# sch.net
KiCad netlist of a schematic drawn in EAGLE
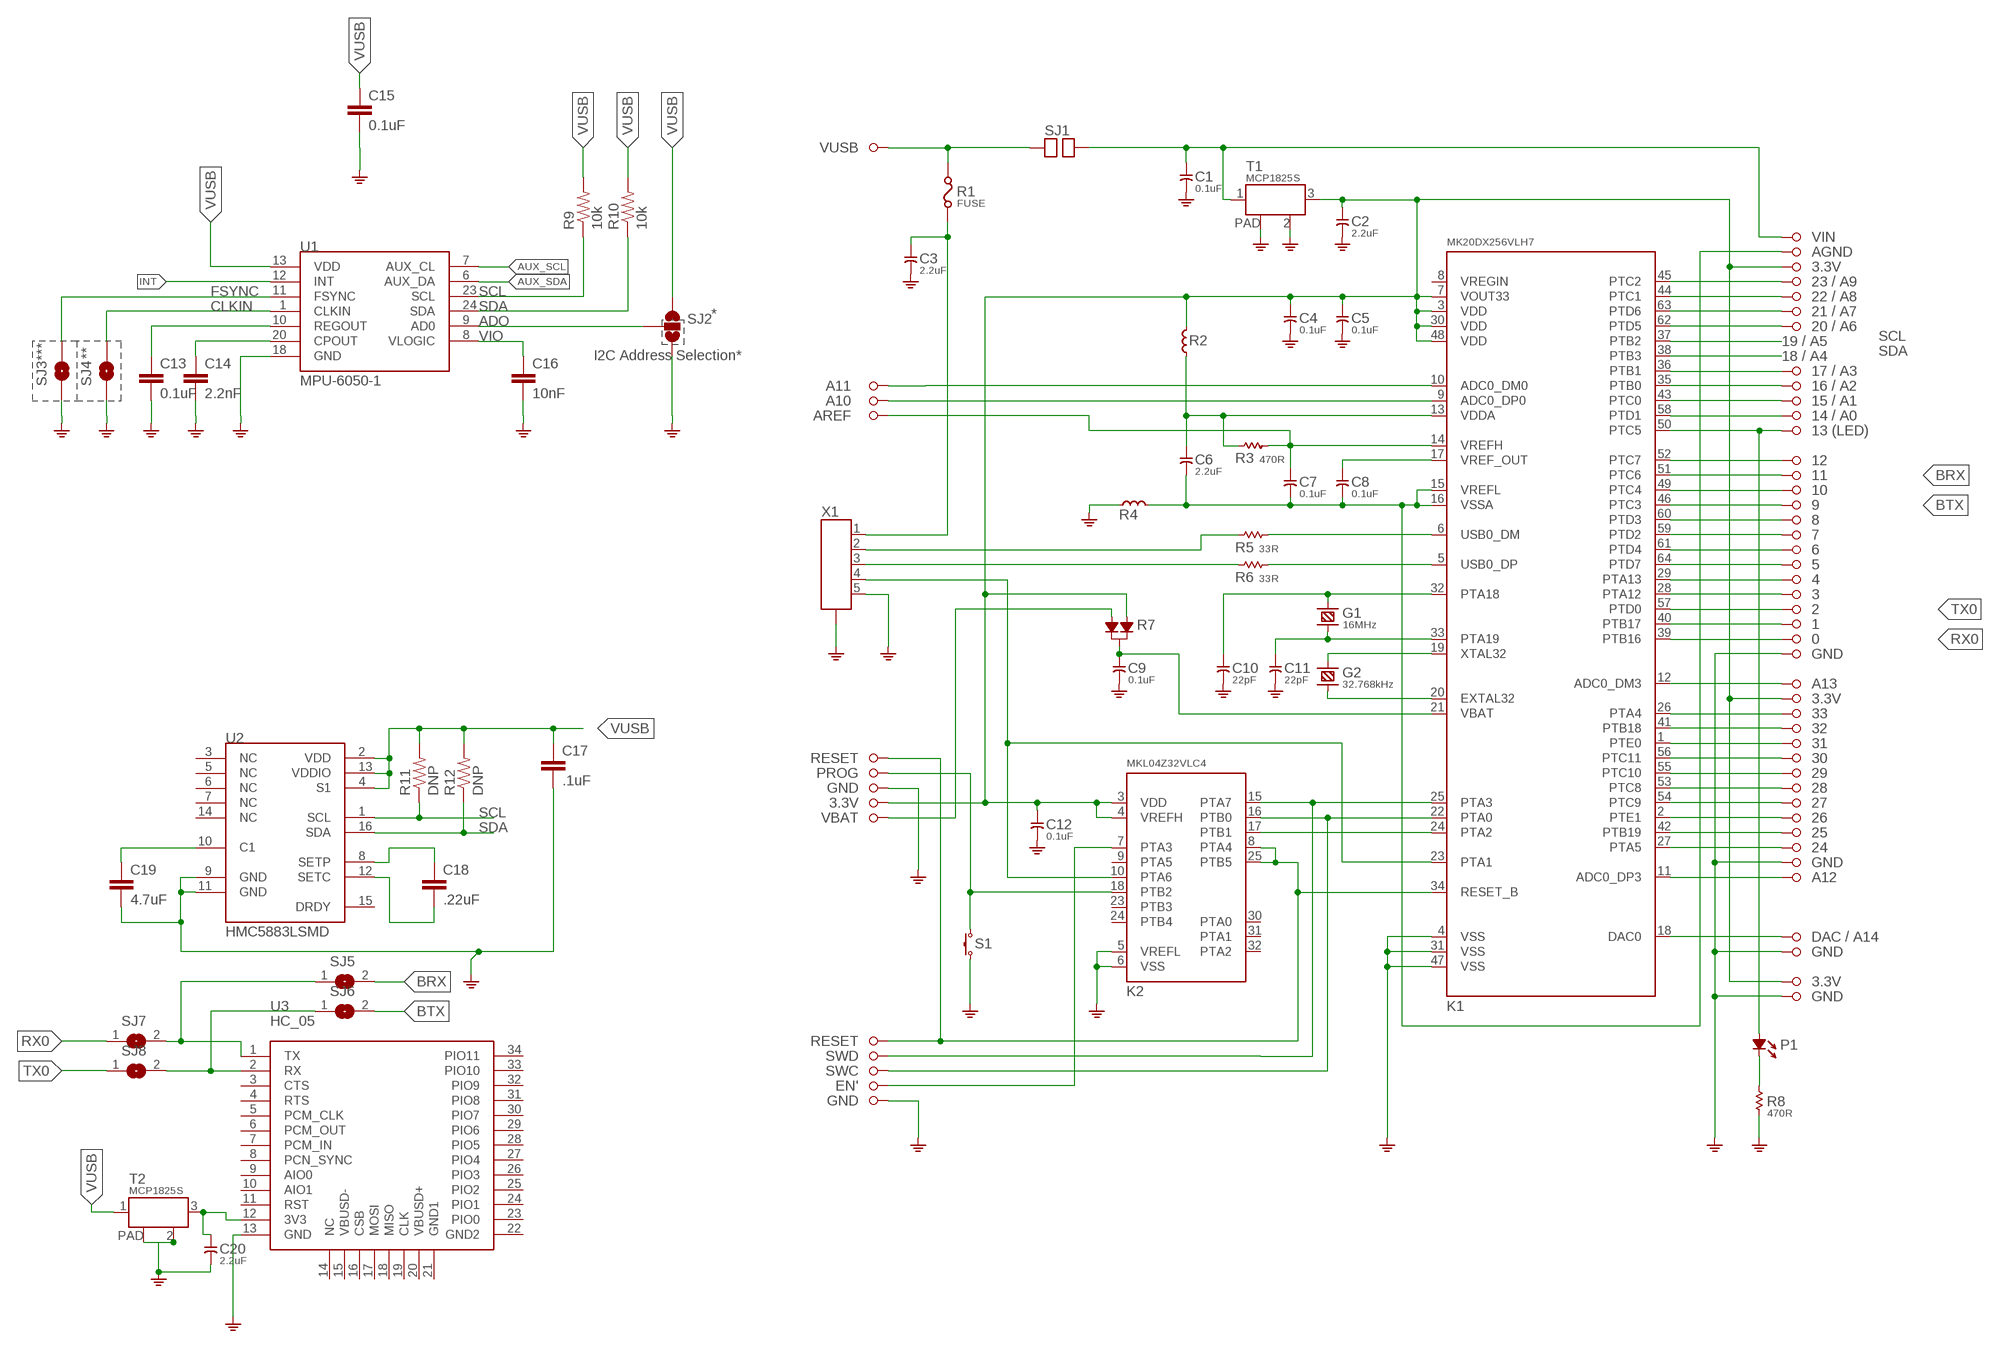
[diagram p0: schematic, sheet 1]

(export (version "E")
  (design (tool "Eeschema 10.0.6"))
  (components
    (comp (ref "C1")
      (value "0.1uF")
      (footprint "eagle-import:C0603")
      (fields (field (name "MF") "Murata Electronics") (field (name "MPN") "GRM188R71C104KA01D"))
      (libsource (lib "eagle-import") (part "CAPACITOR-0.1UF"))
    )
    (comp (ref "C2")
      (value "2.2uF")
      (footprint "eagle-import:C0805")
      (fields (field (name "MF") "Taiyo Yuden") (field (name "MPN") "TMK212B7225KG-TR"))
      (libsource (lib "eagle-import") (part "CAPACITOR-2.2UF"))
    )
    (comp (ref "C3")
      (value "2.2uF")
      (footprint "eagle-import:C0805")
      (fields (field (name "MF") "Taiyo Yuden") (field (name "MPN") "TMK212B7225KG-TR"))
      (libsource (lib "eagle-import") (part "CAPACITOR-2.2UF"))
    )
    (comp (ref "C4")
      (value "0.1uF")
      (footprint "eagle-import:C0603")
      (fields (field (name "MF") "Murata Electronics") (field (name "MPN") "GRM188R71C104KA01D"))
      (libsource (lib "eagle-import") (part "CAPACITOR-0.1UF"))
    )
    (comp (ref "C5")
      (value "0.1uF")
      (footprint "eagle-import:C0603")
      (fields (field (name "MF") "Murata Electronics") (field (name "MPN") "GRM188R71C104KA01D"))
      (libsource (lib "eagle-import") (part "CAPACITOR-0.1UF"))
    )
    (comp (ref "C6")
      (value "2.2uF")
      (footprint "eagle-import:C0805")
      (fields (field (name "MF") "Taiyo Yuden") (field (name "MPN") "TMK212B7225KG-TR"))
      (libsource (lib "eagle-import") (part "CAPACITOR-2.2UF"))
    )
    (comp (ref "C7")
      (value "0.1uF")
      (footprint "eagle-import:C0603")
      (fields (field (name "MF") "Murata Electronics") (field (name "MPN") "GRM188R71C104KA01D"))
      (libsource (lib "eagle-import") (part "CAPACITOR-0.1UF"))
    )
    (comp (ref "C8")
      (value "0.1uF")
      (footprint "eagle-import:C0603")
      (fields (field (name "MF") "Murata Electronics") (field (name "MPN") "GRM188R71C104KA01D"))
      (libsource (lib "eagle-import") (part "CAPACITOR-0.1UF"))
    )
    (comp (ref "C9")
      (value "0.1uF")
      (footprint "eagle-import:C0603")
      (fields (field (name "MF") "Murata Electronics") (field (name "MPN") "GRM188R71C104KA01D"))
      (libsource (lib "eagle-import") (part "CAPACITOR-0.1UF"))
    )
    (comp (ref "C10")
      (value "22pF")
      (footprint "eagle-import:C0603")
      (fields (field (name "MF") "Vishay / Vitramon") (field (name "MPN") "VJ0603A220JXACW1BC"))
      (libsource (lib "eagle-import") (part "CAPACITOR-22PF"))
    )
    (comp (ref "C11")
      (value "22pF")
      (footprint "eagle-import:C0603")
      (fields (field (name "MF") "Vishay / Vitramon") (field (name "MPN") "VJ0603A220JXACW1BC"))
      (libsource (lib "eagle-import") (part "CAPACITOR-22PF"))
    )
    (comp (ref "C12")
      (value "0.1uF")
      (footprint "eagle-import:C0603")
      (fields (field (name "MF") "Murata Electronics") (field (name "MPN") "GRM188R71C104KA01D"))
      (libsource (lib "eagle-import") (part "CAPACITOR-0.1UF"))
    )
    (comp (ref "C13")
      (value "0.1uF")
      (footprint "eagle-import:0603-CAP")
      (libsource (lib "eagle-import") (part "CAP0603-CAP"))
    )
    (comp (ref "C14")
      (value "2.2nF")
      (footprint "eagle-import:0603-CAP")
      (libsource (lib "eagle-import") (part "CAP0603-CAP"))
    )
    (comp (ref "C15")
      (value "0.1uF")
      (footprint "eagle-import:0603-CAP")
      (libsource (lib "eagle-import") (part "CAP0603-CAP"))
    )
    (comp (ref "C16")
      (value "10nF")
      (footprint "eagle-import:0603-CAP")
      (libsource (lib "eagle-import") (part "CAP0603-CAP"))
    )
    (comp (ref "C17")
      (value ".1uF")
      (footprint "eagle-import:0402-CAP")
      (libsource (lib "eagle-import") (part "CAP0402-CAP"))
    )
    (comp (ref "C18")
      (value ".22uF")
      (footprint "eagle-import:0402-CAP")
      (libsource (lib "eagle-import") (part "CAP0402-CAP"))
    )
    (comp (ref "C19")
      (value "4.7uF")
      (footprint "eagle-import:0402-CAP")
      (libsource (lib "eagle-import") (part "CAP0402-CAP"))
    )
    (comp (ref "C20")
      (value "2.2uF")
      (footprint "eagle-import:C0805")
      (fields (field (name "MF") "Taiyo Yuden") (field (name "MPN") "TMK212B7225KG-TR"))
      (libsource (lib "eagle-import") (part "CAPACITOR-2.2UF"))
    )
    (comp (ref "G1")
      (value "16MHz")
      (footprint "eagle-import:HC49US")
      (fields (field (name "MF") "ABRACON") (field (name "MPN") "ABL-16.000MHz-B1U"))
      (libsource (lib "eagle-import") (part "CRYSTAL-HC49US"))
    )
    (comp (ref "G2")
      (value "32.768kHz")
      (footprint "eagle-import:TC26H")
      (fields (field (name "MF") "Citizen FineDevice") (field (name "MPN") " CFS206-32.768KDZF-UB"))
      (libsource (lib "eagle-import") (part "CRYSTAL-TC26H"))
    )
    (comp (ref "K1")
      (value "MK20DX256VLH7")
      (footprint "eagle-import:LQFP64-05")
      (fields (field (name "MF") "NXP"))
      (libsource (lib "eagle-import") (part "MK20DX256VLH7"))
    )
    (comp (ref "K2")
      (value "MKL04Z32VLC4")
      (footprint "eagle-import:LQFP32-08")
      (fields (field (name "MF") "PJRC") (field (name "MPN") "IC_MKL04Z32_TQFP32"))
      (libsource (lib "eagle-import") (part "MKL04Z32VLC4"))
    )
    (comp (ref "P1")
      (value "LED")
      (footprint "eagle-import:LED-0805")
      (fields (field (name "MF") "ROHM Semiconductor") (field (name "MPN") "SML-211DTT86"))
      (libsource (lib "eagle-import") (part "LED"))
    )
    (comp (ref "R1")
      (value "FUSE")
      (footprint "eagle-import:F0805")
      (fields (field (name "MF") "Bel Fuse") (field (name "MPN") "0ZCK0050FF2E"))
      (libsource (lib "eagle-import") (part "FUSE"))
    )
    (comp (ref "R2")
      (value "FERRITE")
      (footprint "eagle-import:L0603")
      (fields (field (name "MF") "Murata Electronics") (field (name "MPN") " BLM18AG601SN1D"))
      (libsource (lib "eagle-import") (part "FERRITE"))
    )
    (comp (ref "R3")
      (value "470R")
      (footprint "eagle-import:R0603")
      (fields (field (name "MF") "Vishay") (field (name "MPN") "CRCW0603470RFKEA"))
      (libsource (lib "eagle-import") (part "RESISTOR-470R"))
    )
    (comp (ref "R4")
      (value "FERRITE")
      (footprint "eagle-import:L0603")
      (fields (field (name "MF") "Murata Electronics") (field (name "MPN") " BLM18AG601SN1D"))
      (libsource (lib "eagle-import") (part "FERRITE"))
    )
    (comp (ref "R5")
      (value "33R")
      (footprint "eagle-import:R0603")
      (fields (field (name "MF") "Panasonic") (field (name "MPN") "ERJ-PA3F33R0V"))
      (libsource (lib "eagle-import") (part "RESISTOR-33R"))
    )
    (comp (ref "R6")
      (value "33R")
      (footprint "eagle-import:R0603")
      (fields (field (name "MF") "Panasonic") (field (name "MPN") "ERJ-PA3F33R0V"))
      (libsource (lib "eagle-import") (part "RESISTOR-33R"))
    )
    (comp (ref "R7")
      (value "DIODE_DUAL")
      (footprint "eagle-import:SOT-23")
      (fields (field (name "MF") "NXP Semiconductors") (field (name "MPN") "BAT54C,215"))
      (libsource (lib "eagle-import") (part "DIODE_DUAL"))
    )
    (comp (ref "R8")
      (value "470R")
      (footprint "eagle-import:R0603")
      (fields (field (name "MF") "Vishay") (field (name "MPN") "CRCW0603470RFKEA"))
      (libsource (lib "eagle-import") (part "RESISTOR-470R"))
    )
    (comp (ref "R9")
      (value "10k")
      (footprint "eagle-import:0603-RES")
      (libsource (lib "eagle-import") (part "RESISTOR0603-RES"))
    )
    (comp (ref "R10")
      (value "10k")
      (footprint "eagle-import:0603-RES")
      (libsource (lib "eagle-import") (part "RESISTOR0603-RES"))
    )
    (comp (ref "R11")
      (value "DNP")
      (footprint "eagle-import:0402-RES")
      (libsource (lib "eagle-import") (part "RESISTOR0402-RES"))
    )
    (comp (ref "R12")
      (value "DNP")
      (footprint "eagle-import:0402-RES")
      (libsource (lib "eagle-import") (part "RESISTOR0402-RES"))
    )
    (comp (ref "S1")
      (value "TACT_SWITCH")
      (footprint "eagle-import:ALPS_SKHH")
      (fields (field (name "MF") "ALPS") (field (name "MPN") "SKHHPKA010"))
      (libsource (lib "eagle-import") (part "TACT_SWITCH"))
    )
    (comp (ref "SJ1")
      (value "SOLDERJUMPER")
      (footprint "eagle-import:SOLDERJUMPER")
      (libsource (lib "eagle-import") (part "SOLDERJUMPER"))
    )
    (comp (ref "SJ2")
      (value "SOLDERJUMPER_2WAYPASTE2&3")
      (footprint "eagle-import:SJ_3_PASTE2&3")
      (libsource (lib "eagle-import") (part "SOLDERJUMPER_2WAYPASTE2&3"))
    )
    (comp (ref "SJ3")
      (value "SOLDERJUMPERTRACE")
      (footprint "eagle-import:SJ_2S-TRACE")
      (libsource (lib "eagle-import") (part "SOLDERJUMPERTRACE"))
    )
    (comp (ref "SJ4")
      (value "SOLDERJUMPERTRACE")
      (footprint "eagle-import:SJ_2S-TRACE")
      (libsource (lib "eagle-import") (part "SOLDERJUMPERTRACE"))
    )
    (comp (ref "SJ5") (value "SJ") (footprint "eagle-import:SJ") (libsource (lib "eagle-import") (part "SJ")))
    (comp (ref "SJ6") (value "SJ") (footprint "eagle-import:SJ") (libsource (lib "eagle-import") (part "SJ")))
    (comp (ref "SJ7") (value "SJ") (footprint "eagle-import:SJ") (libsource (lib "eagle-import") (part "SJ")))
    (comp (ref "SJ8") (value "SJ") (footprint "eagle-import:SJ") (libsource (lib "eagle-import") (part "SJ")))
    (comp (ref "SX1")
      (value "PIN")
      (footprint "eagle-import:PTH_39MIL")
      (libsource (lib "eagle-import") (part "PIN"))
    )
    (comp (ref "SX2")
      (value "PIN")
      (footprint "eagle-import:PTH_39MIL")
      (libsource (lib "eagle-import") (part "PIN"))
    )
    (comp (ref "SX3")
      (value "PIN")
      (footprint "eagle-import:PTH_39MIL")
      (libsource (lib "eagle-import") (part "PIN"))
    )
    (comp (ref "SX4")
      (value "PIN")
      (footprint "eagle-import:PTH_39MIL")
      (libsource (lib "eagle-import") (part "PIN"))
    )
    (comp (ref "SX5")
      (value "PIN")
      (footprint "eagle-import:PTH_39MIL")
      (libsource (lib "eagle-import") (part "PIN"))
    )
    (comp (ref "SX6")
      (value "PIN")
      (footprint "eagle-import:PTH_39MIL")
      (libsource (lib "eagle-import") (part "PIN"))
    )
    (comp (ref "SX7")
      (value "PIN")
      (footprint "eagle-import:PTH_39MIL")
      (libsource (lib "eagle-import") (part "PIN"))
    )
    (comp (ref "SX8")
      (value "PIN")
      (footprint "eagle-import:PTH_39MIL")
      (libsource (lib "eagle-import") (part "PIN"))
    )
    (comp (ref "SX11")
      (value "PIN")
      (footprint "eagle-import:PTH_39MIL")
      (libsource (lib "eagle-import") (part "PIN"))
    )
    (comp (ref "SX12")
      (value "PIN")
      (footprint "eagle-import:PTH_39MIL")
      (libsource (lib "eagle-import") (part "PIN"))
    )
    (comp (ref "SX13")
      (value "PIN")
      (footprint "eagle-import:PTH_39MIL")
      (libsource (lib "eagle-import") (part "PIN"))
    )
    (comp (ref "SX14")
      (value "PIN")
      (footprint "eagle-import:PTH_39MIL")
      (libsource (lib "eagle-import") (part "PIN"))
    )
    (comp (ref "SX15")
      (value "PIN")
      (footprint "eagle-import:PTH_39MIL")
      (libsource (lib "eagle-import") (part "PIN"))
    )
    (comp (ref "SX16")
      (value "PIN")
      (footprint "eagle-import:PTH_39MIL")
      (libsource (lib "eagle-import") (part "PIN"))
    )
    (comp (ref "SX17")
      (value "PIN")
      (footprint "eagle-import:PTH_39MIL")
      (libsource (lib "eagle-import") (part "PIN"))
    )
    (comp (ref "SX18")
      (value "PIN")
      (footprint "eagle-import:PTH_39MIL")
      (libsource (lib "eagle-import") (part "PIN"))
    )
    (comp (ref "SX19")
      (value "PIN")
      (footprint "eagle-import:PTH_39MIL")
      (libsource (lib "eagle-import") (part "PIN"))
    )
    (comp (ref "SX20")
      (value "PIN")
      (footprint "eagle-import:PTH_39MIL")
      (libsource (lib "eagle-import") (part "PIN"))
    )
    (comp (ref "SX21")
      (value "PIN")
      (footprint "eagle-import:PTH_39MIL")
      (libsource (lib "eagle-import") (part "PIN"))
    )
    (comp (ref "SX22")
      (value "PIN")
      (footprint "eagle-import:PTH_39MIL")
      (libsource (lib "eagle-import") (part "PIN"))
    )
    (comp (ref "SX23")
      (value "PIN")
      (footprint "eagle-import:PTH_39MIL")
      (libsource (lib "eagle-import") (part "PIN"))
    )
    (comp (ref "SX24")
      (value "PIN")
      (footprint "eagle-import:PTH_39MIL")
      (libsource (lib "eagle-import") (part "PIN"))
    )
    (comp (ref "SX25")
      (value "PIN")
      (footprint "eagle-import:PTH_39MIL")
      (libsource (lib "eagle-import") (part "PIN"))
    )
    (comp (ref "SX26")
      (value "PIN")
      (footprint "eagle-import:PTH_39MIL")
      (libsource (lib "eagle-import") (part "PIN"))
    )
    (comp (ref "SX27")
      (value "PIN")
      (footprint "eagle-import:PTH_39MIL")
      (libsource (lib "eagle-import") (part "PIN"))
    )
    (comp (ref "SX28")
      (value "PIN")
      (footprint "eagle-import:PTH_39MIL")
      (libsource (lib "eagle-import") (part "PIN"))
    )
    (comp (ref "SX29")
      (value "PIN")
      (footprint "eagle-import:PTH_39MIL")
      (libsource (lib "eagle-import") (part "PIN"))
    )
    (comp (ref "SX30")
      (value "PIN")
      (footprint "eagle-import:PTH_39MIL")
      (libsource (lib "eagle-import") (part "PIN"))
    )
    (comp (ref "SX31")
      (value "PIN")
      (footprint "eagle-import:PTH_39MIL")
      (libsource (lib "eagle-import") (part "PIN"))
    )
    (comp (ref "SX32")
      (value "PIN")
      (footprint "eagle-import:PTH_39MIL")
      (libsource (lib "eagle-import") (part "PIN"))
    )
    (comp (ref "SX33")
      (value "PIN")
      (footprint "eagle-import:PTH_39MIL")
      (libsource (lib "eagle-import") (part "PIN"))
    )
    (comp (ref "SX34")
      (value "PIN")
      (footprint "eagle-import:PTH_39MIL")
      (libsource (lib "eagle-import") (part "PIN"))
    )
    (comp (ref "SX35")
      (value "PIN")
      (footprint "eagle-import:PTH_39MIL")
      (libsource (lib "eagle-import") (part "PIN"))
    )
    (comp (ref "SX36")
      (value "PIN")
      (footprint "eagle-import:PTH_39MIL")
      (libsource (lib "eagle-import") (part "PIN"))
    )
    (comp (ref "SX37")
      (value "PIN")
      (footprint "eagle-import:PTH_39MIL")
      (libsource (lib "eagle-import") (part "PIN"))
    )
    (comp (ref "SX38")
      (value "PIN")
      (footprint "eagle-import:PTH_39MIL")
      (libsource (lib "eagle-import") (part "PIN"))
    )
    (comp (ref "SX39")
      (value "PIN")
      (footprint "eagle-import:PTH_39MIL")
      (libsource (lib "eagle-import") (part "PIN"))
    )
    (comp (ref "SX40")
      (value "PIN")
      (footprint "eagle-import:PTH_39MIL")
      (libsource (lib "eagle-import") (part "PIN"))
    )
    (comp (ref "SX41")
      (value "PIN")
      (footprint "eagle-import:PTH_39MIL")
      (libsource (lib "eagle-import") (part "PIN"))
    )
    (comp (ref "SX42")
      (value "PIN")
      (footprint "eagle-import:PTH_39MIL")
      (libsource (lib "eagle-import") (part "PIN"))
    )
    (comp (ref "SX43")
      (value "PIN")
      (footprint "eagle-import:PTH_39MIL")
      (libsource (lib "eagle-import") (part "PIN"))
    )
    (comp (ref "SX44")
      (value "PIN")
      (footprint "eagle-import:PTH_39MIL")
      (libsource (lib "eagle-import") (part "PIN"))
    )
    (comp (ref "SX45")
      (value "PIN")
      (footprint "eagle-import:PTH_39MIL")
      (libsource (lib "eagle-import") (part "PIN"))
    )
    (comp (ref "SX46")
      (value "PIN")
      (footprint "eagle-import:PTH_39MIL")
      (libsource (lib "eagle-import") (part "PIN"))
    )
    (comp (ref "SX47")
      (value "PIN")
      (footprint "eagle-import:PTH_39MIL")
      (libsource (lib "eagle-import") (part "PIN"))
    )
    (comp (ref "SX48")
      (value "PIN")
      (footprint "eagle-import:PTH_39MIL")
      (libsource (lib "eagle-import") (part "PIN"))
    )
    (comp (ref "SX49")
      (value "PIN")
      (footprint "eagle-import:PTH_39MIL")
      (libsource (lib "eagle-import") (part "PIN"))
    )
    (comp (ref "SX50")
      (value "PIN")
      (footprint "eagle-import:PTH_39MIL")
      (libsource (lib "eagle-import") (part "PIN"))
    )
    (comp (ref "SX51")
      (value "PIN")
      (footprint "eagle-import:PTH_39MIL")
      (libsource (lib "eagle-import") (part "PIN"))
    )
    (comp (ref "SX52")
      (value "PIN")
      (footprint "eagle-import:PTH_39MIL")
      (libsource (lib "eagle-import") (part "PIN"))
    )
    (comp (ref "SX53")
      (value "PIN")
      (footprint "eagle-import:PTH_39MIL")
      (libsource (lib "eagle-import") (part "PIN"))
    )
    (comp (ref "SX54")
      (value "PIN")
      (footprint "eagle-import:PTH_39MIL")
      (libsource (lib "eagle-import") (part "PIN"))
    )
    (comp (ref "SX55")
      (value "PIN")
      (footprint "eagle-import:PTH_39MIL")
      (libsource (lib "eagle-import") (part "PIN"))
    )
    (comp (ref "SX56")
      (value "PIN")
      (footprint "eagle-import:PTH_39MIL")
      (libsource (lib "eagle-import") (part "PIN"))
    )
    (comp (ref "SX57")
      (value "PIN")
      (footprint "eagle-import:PTH_39MIL")
      (libsource (lib "eagle-import") (part "PIN"))
    )
    (comp (ref "SX58")
      (value "PIN")
      (footprint "eagle-import:PTH_39MIL")
      (libsource (lib "eagle-import") (part "PIN"))
    )
    (comp (ref "SX59")
      (value "PIN")
      (footprint "eagle-import:PTH_39MIL")
      (libsource (lib "eagle-import") (part "PIN"))
    )
    (comp (ref "SX60")
      (value "PIN")
      (footprint "eagle-import:PTH_39MIL")
      (libsource (lib "eagle-import") (part "PIN"))
    )
    (comp (ref "T1")
      (value "MCP1825S")
      (footprint "eagle-import:SOT-223")
      (fields (field (name "MF") "Microchip Technology") (field (name "MPN") "MCP1825S-3302E/DB"))
      (libsource (lib "eagle-import") (part "LDO"))
    )
    (comp (ref "T2")
      (value "MCP1825S")
      (footprint "eagle-import:SOT-223")
      (fields (field (name "MF") "Microchip Technology") (field (name "MPN") "MCP1825S-3302E/DB"))
      (libsource (lib "eagle-import") (part "LDO"))
    )
    (comp (ref "U1")
      (value "MPU-6050-1")
      (footprint "eagle-import:QFN-24-4MM2")
      (libsource (lib "eagle-import") (part "MPU-6050-1"))
    )
    (comp (ref "U2")
      (value "HMC5883LSMD")
      (footprint "eagle-import:16LPCC")
      (libsource (lib "eagle-import") (part "HMC5883LSMD"))
    )
    (comp (ref "U3")
      (value "HC_05")
      (footprint "eagle-import:BLUETOOTH_SMD")
      (libsource (lib "eagle-import") (part "HC_05"))
    )
    (comp (ref "X1")
      (value "MINI-USB")
      (footprint "eagle-import:MOLEX_SD-67503-010")
      (fields (field (name "MF") "MOLEX") (field (name "MPN") "0675031020"))
      (libsource (lib "eagle-import") (part "MINI-USBMOLEX_0675031230"))
    )
  )
  (nets
    (net (code "1") (name "/ADO") (class "Default")
      (node (ref "SJ2") (pin "2") (pinfunction "2_2") (pintype "passive"))
      (node (ref "U1") (pin "9") (pinfunction "AD0_9") (pintype "bidirectional"))
    )
    (net (code "2") (name "/CLKIN") (class "Default")
      (node (ref "SJ4") (pin "2") (pinfunction "2_2") (pintype "passive"))
      (node (ref "U1") (pin "1") (pinfunction "CLKIN_1") (pintype "bidirectional"))
    )
    (net (code "3") (name "/FSYNC") (class "Default")
      (node (ref "SJ3") (pin "2") (pinfunction "2_2") (pintype "passive"))
      (node (ref "U1") (pin "11") (pinfunction "FSYNC_11") (pintype "bidirectional"))
    )
    (net (code "4") (name "/SCL") (class "Default")
      (node (ref "K1") (pin "37") (pinfunction "PTB2_37") (pintype "bidirectional"))
      (node (ref "R11") (pin "1") (pinfunction "1_1") (pintype "passive"))
      (node (ref "R9") (pin "1") (pinfunction "1_1") (pintype "passive"))
      (node (ref "U1") (pin "23") (pinfunction "SCL_23") (pintype "bidirectional"))
      (node (ref "U2") (pin "1") (pinfunction "SCL_1") (pintype "bidirectional"))
    )
    (net (code "5") (name "/SDA") (class "Default")
      (node (ref "K1") (pin "38") (pinfunction "PTB3_38") (pintype "bidirectional"))
      (node (ref "R10") (pin "1") (pinfunction "1_1") (pintype "passive"))
      (node (ref "R12") (pin "1") (pinfunction "1_1") (pintype "passive"))
      (node (ref "U1") (pin "24") (pinfunction "SDA_24") (pintype "bidirectional"))
      (node (ref "U2") (pin "16") (pinfunction "SDA_16") (pintype "bidirectional"))
    )
    (net (code "6") (name "/VIO") (class "Default")
      (node (ref "C16") (pin "1") (pinfunction "1_1") (pintype "passive"))
      (node (ref "U1") (pin "8") (pinfunction "VLOGIC_8") (pintype "bidirectional"))
    )
    (net (code "7") (name "AUX_SCL") (class "Default")
      (node (ref "U1") (pin "7") (pinfunction "AUX_CL_7") (pintype "bidirectional"))
    )
    (net (code "8") (name "AUX_SDA") (class "Default")
      (node (ref "U1") (pin "6") (pinfunction "AUX_DA_6") (pintype "bidirectional"))
    )
    (net (code "9") (name "BRX") (class "Default")
      (node (ref "K1") (pin "49") (pinfunction "PTC4_49") (pintype "bidirectional"))
      (node (ref "SJ5") (pin "2") (pinfunction "2_2") (pintype "passive"))
      (node (ref "SX21") (pin "1") (pinfunction "P$1_1") (pintype "bidirectional"))
    )
    (net (code "10") (name "BTX") (class "Default")
      (node (ref "K1") (pin "46") (pinfunction "PTC3_46") (pintype "bidirectional"))
      (node (ref "SJ6") (pin "2") (pinfunction "2_2") (pintype "passive"))
      (node (ref "SX22") (pin "1") (pinfunction "P$1_1") (pintype "bidirectional"))
    )
    (net (code "11") (name "GND") (class "Default")
      (node (ref "C1") (pin "2") (pinfunction "2_2") (pintype "passive"))
      (node (ref "C10") (pin "2") (pinfunction "2_2") (pintype "passive"))
      (node (ref "C11") (pin "2") (pinfunction "2_2") (pintype "passive"))
      (node (ref "C12") (pin "2") (pinfunction "2_2") (pintype "passive"))
      (node (ref "C13") (pin "2") (pinfunction "2_2") (pintype "passive"))
      (node (ref "C14") (pin "2") (pinfunction "2_2") (pintype "passive"))
      (node (ref "C15") (pin "2") (pinfunction "2_2") (pintype "passive"))
      (node (ref "C16") (pin "2") (pinfunction "2_2") (pintype "passive"))
      (node (ref "C17") (pin "2") (pinfunction "2_2") (pintype "passive"))
      (node (ref "C19") (pin "2") (pinfunction "2_2") (pintype "passive"))
      (node (ref "C2") (pin "2") (pinfunction "2_2") (pintype "passive"))
      (node (ref "C20") (pin "2") (pinfunction "2_2") (pintype "passive"))
      (node (ref "C3") (pin "2") (pinfunction "2_2") (pintype "passive"))
      (node (ref "C4") (pin "2") (pinfunction "2_2") (pintype "passive"))
      (node (ref "C5") (pin "2") (pinfunction "2_2") (pintype "passive"))
      (node (ref "C9") (pin "2") (pinfunction "2_2") (pintype "passive"))
      (node (ref "K1") (pin "31") (pinfunction "VSS_31") (pintype "bidirectional"))
      (node (ref "K1") (pin "4") (pinfunction "VSS_4") (pintype "bidirectional"))
      (node (ref "K1") (pin "47") (pinfunction "VSS_47") (pintype "bidirectional"))
      (node (ref "K2") (pin "5") (pinfunction "VREFL_5") (pintype "bidirectional"))
      (node (ref "K2") (pin "6") (pinfunction "VSS_6") (pintype "bidirectional"))
      (node (ref "R4") (pin "1") (pinfunction "1_1") (pintype "passive"))
      (node (ref "R8") (pin "1") (pinfunction "1_1") (pintype "passive"))
      (node (ref "S1") (pin "3") (pinfunction "3_3") (pintype "passive"))
      (node (ref "S1") (pin "4") (pinfunction "3_4") (pintype "passive"))
      (node (ref "SJ2") (pin "3") (pinfunction "3_3") (pintype "passive"))
      (node (ref "SJ3") (pin "1") (pinfunction "1_1") (pintype "passive"))
      (node (ref "SJ4") (pin "1") (pinfunction "1_1") (pintype "passive"))
      (node (ref "SX32") (pin "1") (pinfunction "P$1_1") (pintype "bidirectional"))
      (node (ref "SX42") (pin "1") (pinfunction "P$1_1") (pintype "bidirectional"))
      (node (ref "SX50") (pin "1") (pinfunction "P$1_1") (pintype "bidirectional"))
      (node (ref "SX53") (pin "1") (pinfunction "P$1_1") (pintype "bidirectional"))
      (node (ref "SX55") (pin "1") (pinfunction "P$1_1") (pintype "bidirectional"))
      (node (ref "SX60") (pin "1") (pinfunction "P$1_1") (pintype "bidirectional"))
      (node (ref "T1") (pin "2") (pinfunction "GND_2") (pintype "bidirectional"))
      (node (ref "T1") (pin "PAD") (pinfunction "PAD_PAD") (pintype "bidirectional"))
      (node (ref "T2") (pin "2") (pinfunction "GND_2") (pintype "bidirectional"))
      (node (ref "T2") (pin "PAD") (pinfunction "PAD_PAD") (pintype "bidirectional"))
      (node (ref "U1") (pin "18") (pinfunction "GND_18") (pintype "bidirectional"))
      (node (ref "U2") (pin "11") (pinfunction "GND_11") (pintype "bidirectional"))
      (node (ref "U2") (pin "9") (pinfunction "GND_9") (pintype "bidirectional"))
      (node (ref "U3") (pin "13") (pinfunction "GND_13") (pintype "bidirectional"))
      (node (ref "X1") (pin "5") (pinfunction "5_5") (pintype "input"))
      (node (ref "X1") (pin "P$1") (pinfunction "CASE_P$1") (pintype "input"))
      (node (ref "X1") (pin "P$2") (pinfunction "CASE_P$2") (pintype "input"))
      (node (ref "X1") (pin "P$3") (pinfunction "CASE_P$3") (pintype "input"))
      (node (ref "X1") (pin "P$4") (pinfunction "CASE_P$4") (pintype "input"))
      (node (ref "X1") (pin "P$5") (pinfunction "CASE_P$5") (pintype "input"))
      (node (ref "X1") (pin "P$6") (pinfunction "CASE_P$6") (pintype "input"))
    )
    (net (code "12") (name "INT") (class "Default")
      (node (ref "U1") (pin "12") (pinfunction "INT_12") (pintype "bidirectional"))
    )
    (net (code "13") (name "Net-(C3-Pad1)") (class "Default")
      (node (ref "C3") (pin "1") (pinfunction "1_1") (pintype "passive"))
      (node (ref "R1") (pin "1") (pinfunction "1_1") (pintype "bidirectional"))
      (node (ref "X1") (pin "1") (pinfunction "1_1") (pintype "input"))
    )
    (net (code "14") (name "Net-(G2-1)") (class "Default")
      (node (ref "G2") (pin "2") (pinfunction "1_2") (pintype "passive"))
      (node (ref "K1") (pin "19") (pinfunction "XTAL32_19") (pintype "bidirectional"))
    )
    (net (code "15") (name "Net-(G2-2)") (class "Default")
      (node (ref "G2") (pin "1") (pinfunction "2_1") (pintype "passive"))
      (node (ref "K1") (pin "20") (pinfunction "EXTAL32_20") (pintype "bidirectional"))
    )
    (net (code "16") (name "Net-(K1-ADC0_DM0)") (class "Default")
      (node (ref "K1") (pin "10") (pinfunction "ADC0_DM0_10") (pintype "bidirectional"))
      (node (ref "SX12") (pin "1") (pinfunction "P$1_1") (pintype "bidirectional"))
    )
    (net (code "17") (name "Net-(K1-ADC0_DM3)") (class "Default")
      (node (ref "K1") (pin "12") (pinfunction "ADC0_DM3_12") (pintype "bidirectional"))
      (node (ref "SX33") (pin "1") (pinfunction "P$1_1") (pintype "bidirectional"))
    )
    (net (code "18") (name "Net-(K1-ADC0_DP0)") (class "Default")
      (node (ref "K1") (pin "9") (pinfunction "ADC0_DP0_9") (pintype "bidirectional"))
      (node (ref "SX14") (pin "1") (pinfunction "P$1_1") (pintype "bidirectional"))
    )
    (net (code "19") (name "Net-(K1-ADC0_DP3)") (class "Default")
      (node (ref "K1") (pin "11") (pinfunction "ADC0_DP3_11") (pintype "bidirectional"))
      (node (ref "SX51") (pin "1") (pinfunction "P$1_1") (pintype "bidirectional"))
    )
    (net (code "20") (name "Net-(K1-DAC0)") (class "Default")
      (node (ref "K1") (pin "18") (pinfunction "DAC0_18") (pintype "bidirectional"))
      (node (ref "SX52") (pin "1") (pinfunction "P$1_1") (pintype "bidirectional"))
    )
    (net (code "21") (name "Net-(K1-PTA0)") (class "Default")
      (node (ref "K1") (pin "22") (pinfunction "PTA0_22") (pintype "bidirectional"))
      (node (ref "K2") (pin "16") (pinfunction "PTB0_16") (pintype "bidirectional"))
      (node (ref "SX58") (pin "1") (pinfunction "P$1_1") (pintype "bidirectional"))
    )
    (net (code "22") (name "Net-(K1-PTA1)") (class "Default")
      (node (ref "K1") (pin "23") (pinfunction "PTA1_23") (pintype "bidirectional"))
      (node (ref "K2") (pin "10") (pinfunction "PTA6_10") (pintype "bidirectional"))
      (node (ref "X1") (pin "4") (pinfunction "4_4") (pintype "input"))
    )
    (net (code "23") (name "Net-(K1-PTA2)") (class "Default")
      (node (ref "K1") (pin "24") (pinfunction "PTA2_24") (pintype "bidirectional"))
      (node (ref "K2") (pin "17") (pinfunction "PTB1_17") (pintype "bidirectional"))
    )
    (net (code "24") (name "Net-(K1-PTA3)") (class "Default")
      (node (ref "K1") (pin "25") (pinfunction "PTA3_25") (pintype "bidirectional"))
      (node (ref "K2") (pin "15") (pinfunction "PTA7_15") (pintype "bidirectional"))
      (node (ref "SX57") (pin "1") (pinfunction "P$1_1") (pintype "bidirectional"))
    )
    (net (code "25") (name "Net-(K1-PTA4)") (class "Default")
      (node (ref "K1") (pin "26") (pinfunction "PTA4_26") (pintype "bidirectional"))
      (node (ref "SX35") (pin "1") (pinfunction "P$1_1") (pintype "bidirectional"))
    )
    (net (code "26") (name "Net-(K1-PTA5)") (class "Default")
      (node (ref "K1") (pin "27") (pinfunction "PTA5_27") (pintype "bidirectional"))
      (node (ref "SX49") (pin "1") (pinfunction "P$1_1") (pintype "bidirectional"))
    )
    (net (code "27") (name "Net-(K1-PTA12)") (class "Default")
      (node (ref "K1") (pin "28") (pinfunction "PTA12_28") (pintype "bidirectional"))
      (node (ref "SX28") (pin "1") (pinfunction "P$1_1") (pintype "bidirectional"))
    )
    (net (code "28") (name "Net-(K1-PTA13)") (class "Default")
      (node (ref "K1") (pin "29") (pinfunction "PTA13_29") (pintype "bidirectional"))
      (node (ref "SX27") (pin "1") (pinfunction "P$1_1") (pintype "bidirectional"))
    )
    (net (code "29") (name "Net-(K1-PTA18)") (class "Default")
      (node (ref "C10") (pin "1") (pinfunction "1_1") (pintype "passive"))
      (node (ref "G1") (pin "1") (pinfunction "1_1") (pintype "passive"))
      (node (ref "K1") (pin "32") (pinfunction "PTA18_32") (pintype "bidirectional"))
    )
    (net (code "30") (name "Net-(K1-PTA19)") (class "Default")
      (node (ref "C11") (pin "1") (pinfunction "1_1") (pintype "passive"))
      (node (ref "G1") (pin "2") (pinfunction "2_2") (pintype "passive"))
      (node (ref "K1") (pin "33") (pinfunction "PTA19_33") (pintype "bidirectional"))
    )
    (net (code "31") (name "Net-(K1-PTB0)") (class "Default")
      (node (ref "K1") (pin "35") (pinfunction "PTB0_35") (pintype "bidirectional"))
      (node (ref "SX13") (pin "1") (pinfunction "P$1_1") (pintype "bidirectional"))
    )
    (net (code "32") (name "Net-(K1-PTB1)") (class "Default")
      (node (ref "K1") (pin "36") (pinfunction "PTB1_36") (pintype "bidirectional"))
      (node (ref "SX11") (pin "1") (pinfunction "P$1_1") (pintype "bidirectional"))
    )
    (net (code "33") (name "Net-(K1-PTB18)") (class "Default")
      (node (ref "K1") (pin "41") (pinfunction "PTB18_41") (pintype "bidirectional"))
      (node (ref "SX36") (pin "1") (pinfunction "P$1_1") (pintype "bidirectional"))
    )
    (net (code "34") (name "Net-(K1-PTB19)") (class "Default")
      (node (ref "K1") (pin "42") (pinfunction "PTB19_42") (pintype "bidirectional"))
      (node (ref "SX48") (pin "1") (pinfunction "P$1_1") (pintype "bidirectional"))
    )
    (net (code "35") (name "Net-(K1-PTC0)") (class "Default")
      (node (ref "K1") (pin "43") (pinfunction "PTC0_43") (pintype "bidirectional"))
      (node (ref "SX15") (pin "1") (pinfunction "P$1_1") (pintype "bidirectional"))
    )
    (net (code "36") (name "Net-(K1-PTC1)") (class "Default")
      (node (ref "K1") (pin "44") (pinfunction "PTC1_44") (pintype "bidirectional"))
      (node (ref "SX6") (pin "1") (pinfunction "P$1_1") (pintype "bidirectional"))
    )
    (net (code "37") (name "Net-(K1-PTC2)") (class "Default")
      (node (ref "K1") (pin "45") (pinfunction "PTC2_45") (pintype "bidirectional"))
      (node (ref "SX5") (pin "1") (pinfunction "P$1_1") (pintype "bidirectional"))
    )
    (net (code "38") (name "Net-(K1-PTC5)") (class "Default")
      (node (ref "K1") (pin "50") (pinfunction "PTC5_50") (pintype "bidirectional"))
      (node (ref "P1") (pin "+") (pinfunction "+_+") (pintype "passive"))
      (node (ref "SX18") (pin "1") (pinfunction "P$1_1") (pintype "bidirectional"))
    )
    (net (code "39") (name "Net-(K1-PTC6)") (class "Default")
      (node (ref "K1") (pin "51") (pinfunction "PTC6_51") (pintype "bidirectional"))
      (node (ref "SX20") (pin "1") (pinfunction "P$1_1") (pintype "bidirectional"))
    )
    (net (code "40") (name "Net-(K1-PTC7)") (class "Default")
      (node (ref "K1") (pin "52") (pinfunction "PTC7_52") (pintype "bidirectional"))
      (node (ref "SX19") (pin "1") (pinfunction "P$1_1") (pintype "bidirectional"))
    )
    (net (code "41") (name "Net-(K1-PTC8)") (class "Default")
      (node (ref "K1") (pin "53") (pinfunction "PTC8_53") (pintype "bidirectional"))
      (node (ref "SX43") (pin "1") (pinfunction "P$1_1") (pintype "bidirectional"))
    )
    (net (code "42") (name "Net-(K1-PTC9)") (class "Default")
      (node (ref "K1") (pin "54") (pinfunction "PTC9_54") (pintype "bidirectional"))
      (node (ref "SX45") (pin "1") (pinfunction "P$1_1") (pintype "bidirectional"))
    )
    (net (code "43") (name "Net-(K1-PTC10)") (class "Default")
      (node (ref "K1") (pin "55") (pinfunction "PTC10_55") (pintype "bidirectional"))
      (node (ref "SX41") (pin "1") (pinfunction "P$1_1") (pintype "bidirectional"))
    )
    (net (code "44") (name "Net-(K1-PTC11)") (class "Default")
      (node (ref "K1") (pin "56") (pinfunction "PTC11_56") (pintype "bidirectional"))
      (node (ref "SX39") (pin "1") (pinfunction "P$1_1") (pintype "bidirectional"))
    )
    (net (code "45") (name "Net-(K1-PTD0)") (class "Default")
      (node (ref "K1") (pin "57") (pinfunction "PTD0_57") (pintype "bidirectional"))
      (node (ref "SX29") (pin "1") (pinfunction "P$1_1") (pintype "bidirectional"))
    )
    (net (code "46") (name "Net-(K1-PTD1)") (class "Default")
      (node (ref "K1") (pin "58") (pinfunction "PTD1_58") (pintype "bidirectional"))
      (node (ref "SX17") (pin "1") (pinfunction "P$1_1") (pintype "bidirectional"))
    )
    (net (code "47") (name "Net-(K1-PTD2)") (class "Default")
      (node (ref "K1") (pin "59") (pinfunction "PTD2_59") (pintype "bidirectional"))
      (node (ref "SX24") (pin "1") (pinfunction "P$1_1") (pintype "bidirectional"))
    )
    (net (code "48") (name "Net-(K1-PTD3)") (class "Default")
      (node (ref "K1") (pin "60") (pinfunction "PTD3_60") (pintype "bidirectional"))
      (node (ref "SX23") (pin "1") (pinfunction "P$1_1") (pintype "bidirectional"))
    )
    (net (code "49") (name "Net-(K1-PTD4)") (class "Default")
      (node (ref "K1") (pin "61") (pinfunction "PTD4_61") (pintype "bidirectional"))
      (node (ref "SX25") (pin "1") (pinfunction "P$1_1") (pintype "bidirectional"))
    )
    (net (code "50") (name "Net-(K1-PTD5)") (class "Default")
      (node (ref "K1") (pin "62") (pinfunction "PTD5_62") (pintype "bidirectional"))
      (node (ref "SX8") (pin "1") (pinfunction "P$1_1") (pintype "bidirectional"))
    )
    (net (code "51") (name "Net-(K1-PTD6)") (class "Default")
      (node (ref "K1") (pin "63") (pinfunction "PTD6_63") (pintype "bidirectional"))
      (node (ref "SX7") (pin "1") (pinfunction "P$1_1") (pintype "bidirectional"))
    )
    (net (code "52") (name "Net-(K1-PTD7)") (class "Default")
      (node (ref "K1") (pin "64") (pinfunction "PTD7_64") (pintype "bidirectional"))
      (node (ref "SX26") (pin "1") (pinfunction "P$1_1") (pintype "bidirectional"))
    )
    (net (code "53") (name "Net-(K1-PTE0)") (class "Default")
      (node (ref "K1") (pin "1") (pinfunction "PTE0_1") (pintype "bidirectional"))
      (node (ref "SX37") (pin "1") (pinfunction "P$1_1") (pintype "bidirectional"))
    )
    (net (code "54") (name "Net-(K1-PTE1)") (class "Default")
      (node (ref "K1") (pin "2") (pinfunction "PTE1_2") (pintype "bidirectional"))
      (node (ref "SX47") (pin "1") (pinfunction "P$1_1") (pintype "bidirectional"))
    )
    (net (code "55") (name "Net-(K1-RESET_B)") (class "Default")
      (node (ref "K1") (pin "34") (pinfunction "RESET_B_34") (pintype "bidirectional"))
      (node (ref "K2") (pin "25") (pinfunction "PTB5_25") (pintype "bidirectional"))
      (node (ref "K2") (pin "8") (pinfunction "PTA4_8") (pintype "bidirectional"))
      (node (ref "SX38") (pin "1") (pinfunction "P$1_1") (pintype "bidirectional"))
      (node (ref "SX56") (pin "1") (pinfunction "P$1_1") (pintype "bidirectional"))
    )
    (net (code "56") (name "Net-(K1-USB0_DM)") (class "Default")
      (node (ref "K1") (pin "6") (pinfunction "USB0_DM_6") (pintype "bidirectional"))
      (node (ref "R5") (pin "2") (pinfunction "2_2") (pintype "passive"))
    )
    (net (code "57") (name "Net-(K1-USB0_DP)") (class "Default")
      (node (ref "K1") (pin "5") (pinfunction "USB0_DP_5") (pintype "bidirectional"))
      (node (ref "R6") (pin "2") (pinfunction "2_2") (pintype "passive"))
    )
    (net (code "58") (name "Net-(K1-VBAT)") (class "Default")
      (node (ref "C9") (pin "1") (pinfunction "1_1") (pintype "passive"))
      (node (ref "K1") (pin "21") (pinfunction "VBAT_21") (pintype "bidirectional"))
      (node (ref "R7") (pin "3") (pinfunction "3_3") (pintype "bidirectional"))
    )
    (net (code "59") (name "Net-(K1-VDDA)") (class "Default")
      (node (ref "C6") (pin "1") (pinfunction "1_1") (pintype "passive"))
      (node (ref "K1") (pin "13") (pinfunction "VDDA_13") (pintype "bidirectional"))
      (node (ref "R2") (pin "1") (pinfunction "1_1") (pintype "passive"))
      (node (ref "R3") (pin "1") (pinfunction "1_1") (pintype "passive"))
    )
    (net (code "60") (name "Net-(K1-VOUT33)") (class "Default")
      (node (ref "C12") (pin "1") (pinfunction "1_1") (pintype "passive"))
      (node (ref "C2") (pin "1") (pinfunction "1_1") (pintype "passive"))
      (node (ref "C4") (pin "1") (pinfunction "1_1") (pintype "passive"))
      (node (ref "C5") (pin "1") (pinfunction "1_1") (pintype "passive"))
      (node (ref "K1") (pin "3") (pinfunction "VDD_3") (pintype "bidirectional"))
      (node (ref "K1") (pin "30") (pinfunction "VDD_30") (pintype "bidirectional"))
      (node (ref "K1") (pin "48") (pinfunction "VDD_48") (pintype "bidirectional"))
      (node (ref "K1") (pin "7") (pinfunction "VOUT33_7") (pintype "bidirectional"))
      (node (ref "K2") (pin "3") (pinfunction "VDD_3") (pintype "bidirectional"))
      (node (ref "K2") (pin "4") (pinfunction "VREFH_4") (pintype "bidirectional"))
      (node (ref "R2") (pin "2") (pinfunction "2_2") (pintype "passive"))
      (node (ref "R7") (pin "1") (pinfunction "1_1") (pintype "bidirectional"))
      (node (ref "SX34") (pin "1") (pinfunction "P$1_1") (pintype "bidirectional"))
      (node (ref "SX4") (pin "1") (pinfunction "P$1_1") (pintype "bidirectional"))
      (node (ref "SX44") (pin "1") (pinfunction "P$1_1") (pintype "bidirectional"))
      (node (ref "SX54") (pin "1") (pinfunction "P$1_1") (pintype "bidirectional"))
      (node (ref "T1") (pin "3") (pinfunction "OUT_3") (pintype "bidirectional"))
    )
    (net (code "61") (name "Net-(K1-VREFH)") (class "Default")
      (node (ref "C7") (pin "1") (pinfunction "1_1") (pintype "passive"))
      (node (ref "K1") (pin "14") (pinfunction "VREFH_14") (pintype "bidirectional"))
      (node (ref "R3") (pin "2") (pinfunction "2_2") (pintype "passive"))
      (node (ref "SX16") (pin "1") (pinfunction "P$1_1") (pintype "bidirectional"))
    )
    (net (code "62") (name "Net-(K1-VREFL)") (class "Default")
      (node (ref "C6") (pin "2") (pinfunction "2_2") (pintype "passive"))
      (node (ref "C7") (pin "2") (pinfunction "2_2") (pintype "passive"))
      (node (ref "C8") (pin "2") (pinfunction "2_2") (pintype "passive"))
      (node (ref "K1") (pin "15") (pinfunction "VREFL_15") (pintype "bidirectional"))
      (node (ref "K1") (pin "16") (pinfunction "VSSA_16") (pintype "bidirectional"))
      (node (ref "R4") (pin "2") (pinfunction "2_2") (pintype "passive"))
      (node (ref "SX3") (pin "1") (pinfunction "P$1_1") (pintype "bidirectional"))
    )
    (net (code "63") (name "Net-(K1-VREF_OUT)") (class "Default")
      (node (ref "C8") (pin "1") (pinfunction "1_1") (pintype "passive"))
      (node (ref "K1") (pin "17") (pinfunction "VREF_OUT_17") (pintype "bidirectional"))
    )
    (net (code "64") (name "Net-(K2-PTA3)") (class "Default")
      (node (ref "K2") (pin "7") (pinfunction "PTA3_7") (pintype "bidirectional"))
      (node (ref "SX59") (pin "1") (pinfunction "P$1_1") (pintype "bidirectional"))
    )
    (net (code "65") (name "Net-(K2-PTB2)") (class "Default")
      (node (ref "K2") (pin "18") (pinfunction "PTB2_18") (pintype "bidirectional"))
      (node (ref "S1") (pin "1") (pinfunction "1_1") (pintype "passive"))
      (node (ref "S1") (pin "2") (pinfunction "1_2") (pintype "passive"))
      (node (ref "SX40") (pin "1") (pinfunction "P$1_1") (pintype "bidirectional"))
    )
    (net (code "66") (name "Net-(P1-Pad-)") (class "Default")
      (node (ref "P1") (pin "-") (pinfunction "-_-") (pintype "passive"))
      (node (ref "R8") (pin "2") (pinfunction "2_2") (pintype "passive"))
    )
    (net (code "67") (name "Net-(R5-Pad1)") (class "Default")
      (node (ref "R5") (pin "1") (pinfunction "1_1") (pintype "passive"))
      (node (ref "X1") (pin "2") (pinfunction "2_2") (pintype "input"))
    )
    (net (code "68") (name "Net-(R6-Pad1)") (class "Default")
      (node (ref "R6") (pin "1") (pinfunction "1_1") (pintype "passive"))
      (node (ref "X1") (pin "3") (pinfunction "3_3") (pintype "input"))
    )
    (net (code "69") (name "Net-(SX1-P$1)") (class "Default")
      (node (ref "R1") (pin "2") (pinfunction "2_2") (pintype "bidirectional"))
      (node (ref "SJ1") (pin "1") (pinfunction "1_1") (pintype "passive"))
      (node (ref "SX1") (pin "1") (pinfunction "P$1_1") (pintype "bidirectional"))
    )
    (net (code "70") (name "Net-(SX2-P$1)") (class "Default")
      (node (ref "C1") (pin "1") (pinfunction "1_1") (pintype "passive"))
      (node (ref "SJ1") (pin "2") (pinfunction "2_2") (pintype "passive"))
      (node (ref "SX2") (pin "1") (pinfunction "P$1_1") (pintype "bidirectional"))
      (node (ref "T1") (pin "1") (pinfunction "IN_1") (pintype "bidirectional"))
    )
    (net (code "71") (name "Net-(SX46-P$1)") (class "Default")
      (node (ref "R7") (pin "2") (pinfunction "2_2") (pintype "bidirectional"))
      (node (ref "SX46") (pin "1") (pinfunction "P$1_1") (pintype "bidirectional"))
    )
    (net (code "72") (name "Net-(T2-OUT)") (class "Default")
      (node (ref "C20") (pin "1") (pinfunction "1_1") (pintype "passive"))
      (node (ref "T2") (pin "3") (pinfunction "OUT_3") (pintype "bidirectional"))
      (node (ref "U3") (pin "12") (pinfunction "3V3_12") (pintype "bidirectional"))
    )
    (net (code "73") (name "Net-(U1-CPOUT)") (class "Default")
      (node (ref "C14") (pin "1") (pinfunction "1_1") (pintype "passive"))
      (node (ref "U1") (pin "20") (pinfunction "CPOUT_20") (pintype "bidirectional"))
    )
    (net (code "74") (name "Net-(U1-REGOUT)") (class "Default")
      (node (ref "C13") (pin "1") (pinfunction "1_1") (pintype "passive"))
      (node (ref "U1") (pin "10") (pinfunction "REGOUT_10") (pintype "bidirectional"))
    )
    (net (code "75") (name "Net-(U2-C1)") (class "Default")
      (node (ref "C19") (pin "1") (pinfunction "1_1") (pintype "passive"))
      (node (ref "U2") (pin "10") (pinfunction "C1_10") (pintype "bidirectional"))
    )
    (net (code "76") (name "Net-(U2-SETC)") (class "Default")
      (node (ref "C18") (pin "2") (pinfunction "2_2") (pintype "passive"))
      (node (ref "U2") (pin "12") (pinfunction "SETC_12") (pintype "bidirectional"))
    )
    (net (code "77") (name "Net-(U2-SETP)") (class "Default")
      (node (ref "C18") (pin "1") (pinfunction "1_1") (pintype "passive"))
      (node (ref "U2") (pin "8") (pinfunction "SETP_8") (pintype "bidirectional"))
    )
    (net (code "78") (name "Net-(U3-RX)") (class "Default")
      (node (ref "SJ6") (pin "1") (pinfunction "1_1") (pintype "passive"))
      (node (ref "SJ8") (pin "2") (pinfunction "2_2") (pintype "passive"))
      (node (ref "U3") (pin "2") (pinfunction "RX_2") (pintype "bidirectional"))
    )
    (net (code "79") (name "Net-(U3-TX)") (class "Default")
      (node (ref "SJ5") (pin "1") (pinfunction "1_1") (pintype "passive"))
      (node (ref "SJ7") (pin "2") (pinfunction "2_2") (pintype "passive"))
      (node (ref "U3") (pin "1") (pinfunction "TX_1") (pintype "bidirectional"))
    )
    (net (code "80") (name "RX0") (class "Default")
      (node (ref "K1") (pin "39") (pinfunction "PTB16_39") (pintype "bidirectional"))
      (node (ref "SJ7") (pin "1") (pinfunction "1_1") (pintype "passive"))
      (node (ref "SX31") (pin "1") (pinfunction "P$1_1") (pintype "bidirectional"))
    )
    (net (code "81") (name "TX0") (class "Default")
      (node (ref "K1") (pin "40") (pinfunction "PTB17_40") (pintype "bidirectional"))
      (node (ref "SJ8") (pin "1") (pinfunction "1_1") (pintype "passive"))
      (node (ref "SX30") (pin "1") (pinfunction "P$1_1") (pintype "bidirectional"))
    )
    (net (code "82") (name "VUSB") (class "Default")
      (node (ref "C15") (pin "1") (pinfunction "1_1") (pintype "passive"))
      (node (ref "C17") (pin "1") (pinfunction "1_1") (pintype "passive"))
      (node (ref "R10") (pin "2") (pinfunction "2_2") (pintype "passive"))
      (node (ref "R11") (pin "2") (pinfunction "2_2") (pintype "passive"))
      (node (ref "R12") (pin "2") (pinfunction "2_2") (pintype "passive"))
      (node (ref "R9") (pin "2") (pinfunction "2_2") (pintype "passive"))
      (node (ref "SJ2") (pin "1") (pinfunction "1_1") (pintype "passive"))
      (node (ref "T2") (pin "1") (pinfunction "IN_1") (pintype "bidirectional"))
      (node (ref "U1") (pin "13") (pinfunction "VDD_13") (pintype "bidirectional"))
      (node (ref "U2") (pin "13") (pinfunction "VDDIO_13") (pintype "bidirectional"))
      (node (ref "U2") (pin "2") (pinfunction "VDD_2") (pintype "bidirectional"))
      (node (ref "U2") (pin "4") (pinfunction "S1_4") (pintype "bidirectional"))
    )
    (net (code "83") (name "unconnected-(K1-VREGIN-Pad8)") (class "Default")
      (node (ref "K1") (pin "8") (pinfunction "VREGIN_8") (pintype "bidirectional"))
    )
    (net (code "84") (name "unconnected-(K2-PTA0-Pad30)") (class "Default")
      (node (ref "K2") (pin "30") (pinfunction "PTA0_30") (pintype "bidirectional"))
    )
    (net (code "85") (name "unconnected-(K2-PTA1-Pad31)") (class "Default")
      (node (ref "K2") (pin "31") (pinfunction "PTA1_31") (pintype "bidirectional"))
    )
    (net (code "86") (name "unconnected-(K2-PTA2-Pad32)") (class "Default")
      (node (ref "K2") (pin "32") (pinfunction "PTA2_32") (pintype "bidirectional"))
    )
    (net (code "87") (name "unconnected-(K2-PTA5-Pad9)") (class "Default")
      (node (ref "K2") (pin "9") (pinfunction "PTA5_9") (pintype "bidirectional"))
    )
    (net (code "88") (name "unconnected-(K2-PTB3-Pad23)") (class "Default")
      (node (ref "K2") (pin "23") (pinfunction "PTB3_23") (pintype "bidirectional"))
    )
    (net (code "89") (name "unconnected-(K2-PTB4-Pad24)") (class "Default")
      (node (ref "K2") (pin "24") (pinfunction "PTB4_24") (pintype "bidirectional"))
    )
    (net (code "90") (name "unconnected-(U2-DRDY-Pad15)") (class "Default")
      (node (ref "U2") (pin "15") (pinfunction "DRDY_15") (pintype "bidirectional"))
    )
    (net (code "91") (name "unconnected-(U2-NC-Pad3)") (class "Default")
      (node (ref "U2") (pin "3") (pinfunction "NC_3") (pintype "bidirectional"))
    )
    (net (code "92") (name "unconnected-(U2-NC-Pad5)") (class "Default")
      (node (ref "U2") (pin "5") (pinfunction "NC_5") (pintype "bidirectional"))
    )
    (net (code "93") (name "unconnected-(U2-NC-Pad6)") (class "Default")
      (node (ref "U2") (pin "6") (pinfunction "NC_6") (pintype "bidirectional"))
    )
    (net (code "94") (name "unconnected-(U2-NC-Pad7)") (class "Default")
      (node (ref "U2") (pin "7") (pinfunction "NC_7") (pintype "bidirectional"))
    )
    (net (code "95") (name "unconnected-(U2-NC-Pad14)") (class "Default")
      (node (ref "U2") (pin "14") (pinfunction "NC_14") (pintype "bidirectional"))
    )
    (net (code "96") (name "unconnected-(U3-AIO0-Pad9)") (class "Default")
      (node (ref "U3") (pin "9") (pinfunction "AIO0_9") (pintype "bidirectional"))
    )
    (net (code "97") (name "unconnected-(U3-AIO1-Pad10)") (class "Default")
      (node (ref "U3") (pin "10") (pinfunction "AIO1_10") (pintype "bidirectional"))
    )
    (net (code "98") (name "unconnected-(U3-CLK-Pad19)") (class "Default")
      (node (ref "U3") (pin "19") (pinfunction "CLK_19") (pintype "bidirectional"))
    )
    (net (code "99") (name "unconnected-(U3-CSB-Pad16)") (class "Default")
      (node (ref "U3") (pin "16") (pinfunction "CSB_16") (pintype "bidirectional"))
    )
    (net (code "100") (name "unconnected-(U3-CTS-Pad3)") (class "Default")
      (node (ref "U3") (pin "3") (pinfunction "CTS_3") (pintype "bidirectional"))
    )
    (net (code "101") (name "unconnected-(U3-GND1-Pad21)") (class "Default")
      (node (ref "U3") (pin "21") (pinfunction "GND1_21") (pintype "bidirectional"))
    )
    (net (code "102") (name "unconnected-(U3-GND2-Pad22)") (class "Default")
      (node (ref "U3") (pin "22") (pinfunction "GND2_22") (pintype "bidirectional"))
    )
    (net (code "103") (name "unconnected-(U3-MISO-Pad18)") (class "Default")
      (node (ref "U3") (pin "18") (pinfunction "MISO_18") (pintype "bidirectional"))
    )
    (net (code "104") (name "unconnected-(U3-MOSI-Pad17)") (class "Default")
      (node (ref "U3") (pin "17") (pinfunction "MOSI_17") (pintype "bidirectional"))
    )
    (net (code "105") (name "unconnected-(U3-NC-Pad14)") (class "Default")
      (node (ref "U3") (pin "14") (pinfunction "NC_14") (pintype "bidirectional"))
    )
    (net (code "106") (name "unconnected-(U3-PCM_CLK-Pad5)") (class "Default")
      (node (ref "U3") (pin "5") (pinfunction "PCM_CLK_5") (pintype "bidirectional"))
    )
    (net (code "107") (name "unconnected-(U3-PCM_IN-Pad7)") (class "Default")
      (node (ref "U3") (pin "7") (pinfunction "PCM_IN_7") (pintype "bidirectional"))
    )
    (net (code "108") (name "unconnected-(U3-PCM_OUT-Pad6)") (class "Default")
      (node (ref "U3") (pin "6") (pinfunction "PCM_OUT_6") (pintype "bidirectional"))
    )
    (net (code "109") (name "unconnected-(U3-PCN_SYNC-Pad8)") (class "Default")
      (node (ref "U3") (pin "8") (pinfunction "PCN_SYNC_8") (pintype "bidirectional"))
    )
    (net (code "110") (name "unconnected-(U3-PIO0-Pad23)") (class "Default")
      (node (ref "U3") (pin "23") (pinfunction "PIO0_23") (pintype "bidirectional"))
    )
    (net (code "111") (name "unconnected-(U3-PIO1-Pad24)") (class "Default")
      (node (ref "U3") (pin "24") (pinfunction "PIO1_24") (pintype "bidirectional"))
    )
    (net (code "112") (name "unconnected-(U3-PIO2-Pad25)") (class "Default")
      (node (ref "U3") (pin "25") (pinfunction "PIO2_25") (pintype "bidirectional"))
    )
    (net (code "113") (name "unconnected-(U3-PIO3-Pad26)") (class "Default")
      (node (ref "U3") (pin "26") (pinfunction "PIO3_26") (pintype "bidirectional"))
    )
    (net (code "114") (name "unconnected-(U3-PIO4-Pad27)") (class "Default")
      (node (ref "U3") (pin "27") (pinfunction "PIO4_27") (pintype "bidirectional"))
    )
    (net (code "115") (name "unconnected-(U3-PIO5-Pad28)") (class "Default")
      (node (ref "U3") (pin "28") (pinfunction "PIO5_28") (pintype "bidirectional"))
    )
    (net (code "116") (name "unconnected-(U3-PIO6-Pad29)") (class "Default")
      (node (ref "U3") (pin "29") (pinfunction "PIO6_29") (pintype "bidirectional"))
    )
    (net (code "117") (name "unconnected-(U3-PIO7-Pad30)") (class "Default")
      (node (ref "U3") (pin "30") (pinfunction "PIO7_30") (pintype "bidirectional"))
    )
    (net (code "118") (name "unconnected-(U3-PIO8-Pad31)") (class "Default")
      (node (ref "U3") (pin "31") (pinfunction "PIO8_31") (pintype "bidirectional"))
    )
    (net (code "119") (name "unconnected-(U3-PIO9-Pad32)") (class "Default")
      (node (ref "U3") (pin "32") (pinfunction "PIO9_32") (pintype "bidirectional"))
    )
    (net (code "120") (name "unconnected-(U3-PIO10-Pad33)") (class "Default")
      (node (ref "U3") (pin "33") (pinfunction "PIO10_33") (pintype "bidirectional"))
    )
    (net (code "121") (name "unconnected-(U3-PIO11-Pad34)") (class "Default")
      (node (ref "U3") (pin "34") (pinfunction "PIO11_34") (pintype "bidirectional"))
    )
    (net (code "122") (name "unconnected-(U3-RST-Pad11)") (class "Default")
      (node (ref "U3") (pin "11") (pinfunction "RST_11") (pintype "bidirectional"))
    )
    (net (code "123") (name "unconnected-(U3-RTS-Pad4)") (class "Default")
      (node (ref "U3") (pin "4") (pinfunction "RTS_4") (pintype "bidirectional"))
    )
    (net (code "124") (name "unconnected-(U3-VBUSD+-Pad20)") (class "Default")
      (node (ref "U3") (pin "20") (pinfunction "VBUSD+_20") (pintype "bidirectional"))
    )
    (net (code "125") (name "unconnected-(U3-VBUSD--Pad15)") (class "Default")
      (node (ref "U3") (pin "15") (pinfunction "VBUSD-_15") (pintype "bidirectional"))
    )
  )
)
